# lab5.net
KiCad netlist of a schematic drawn in EAGLE
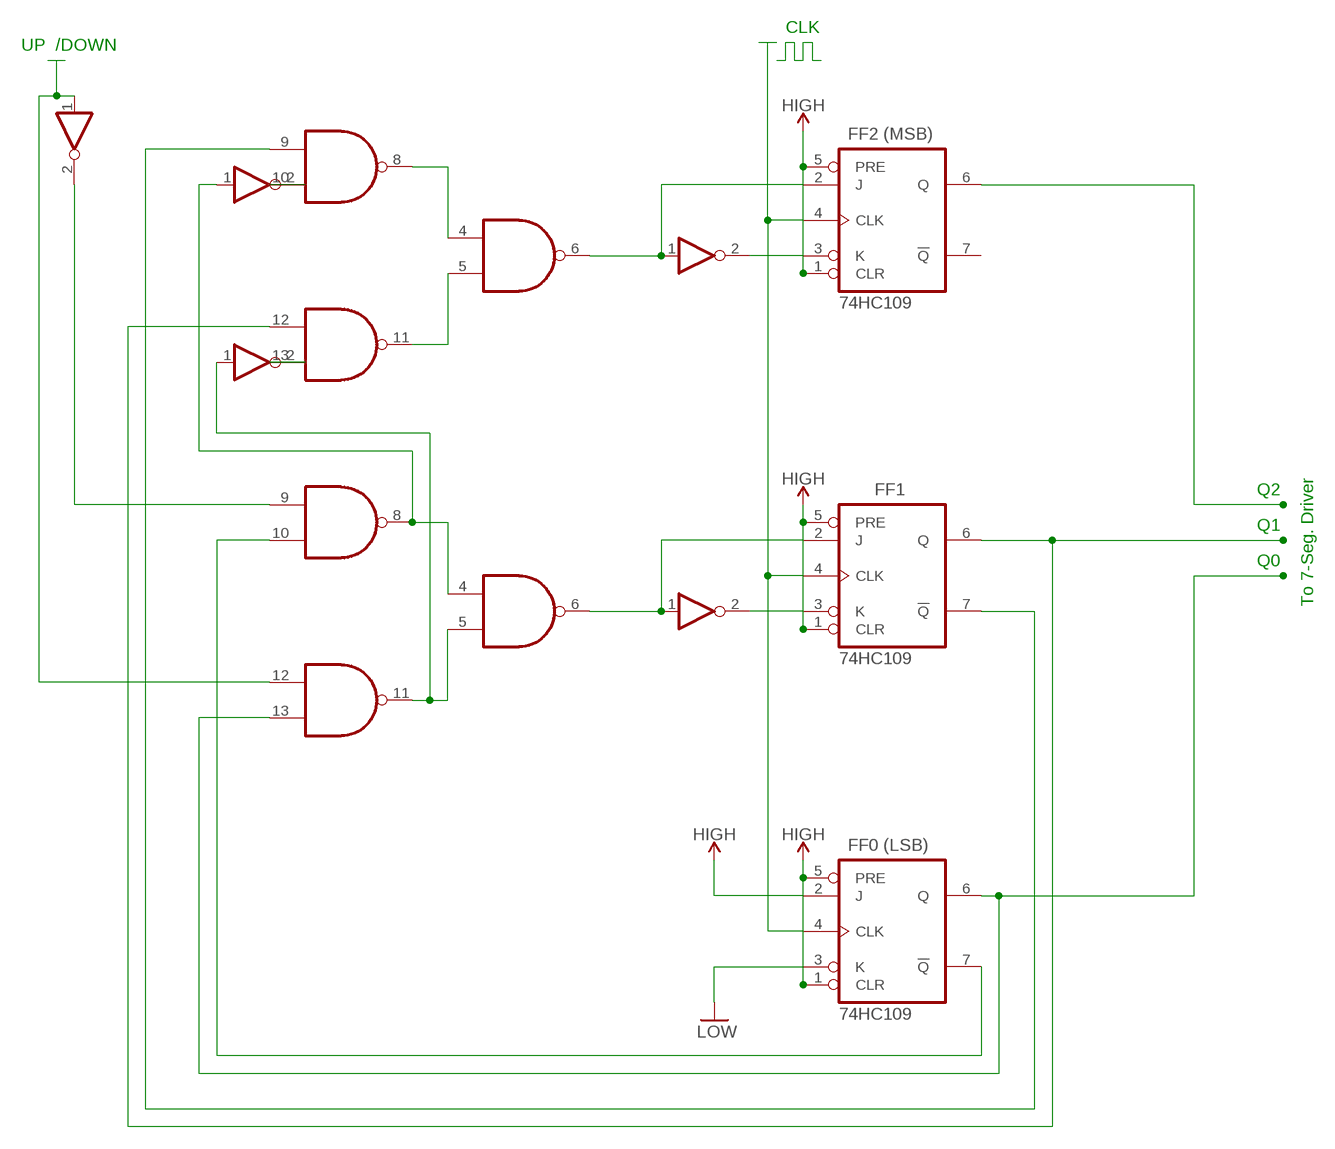
[diagram p0: schematic, sheet 1, part 1 of 2]
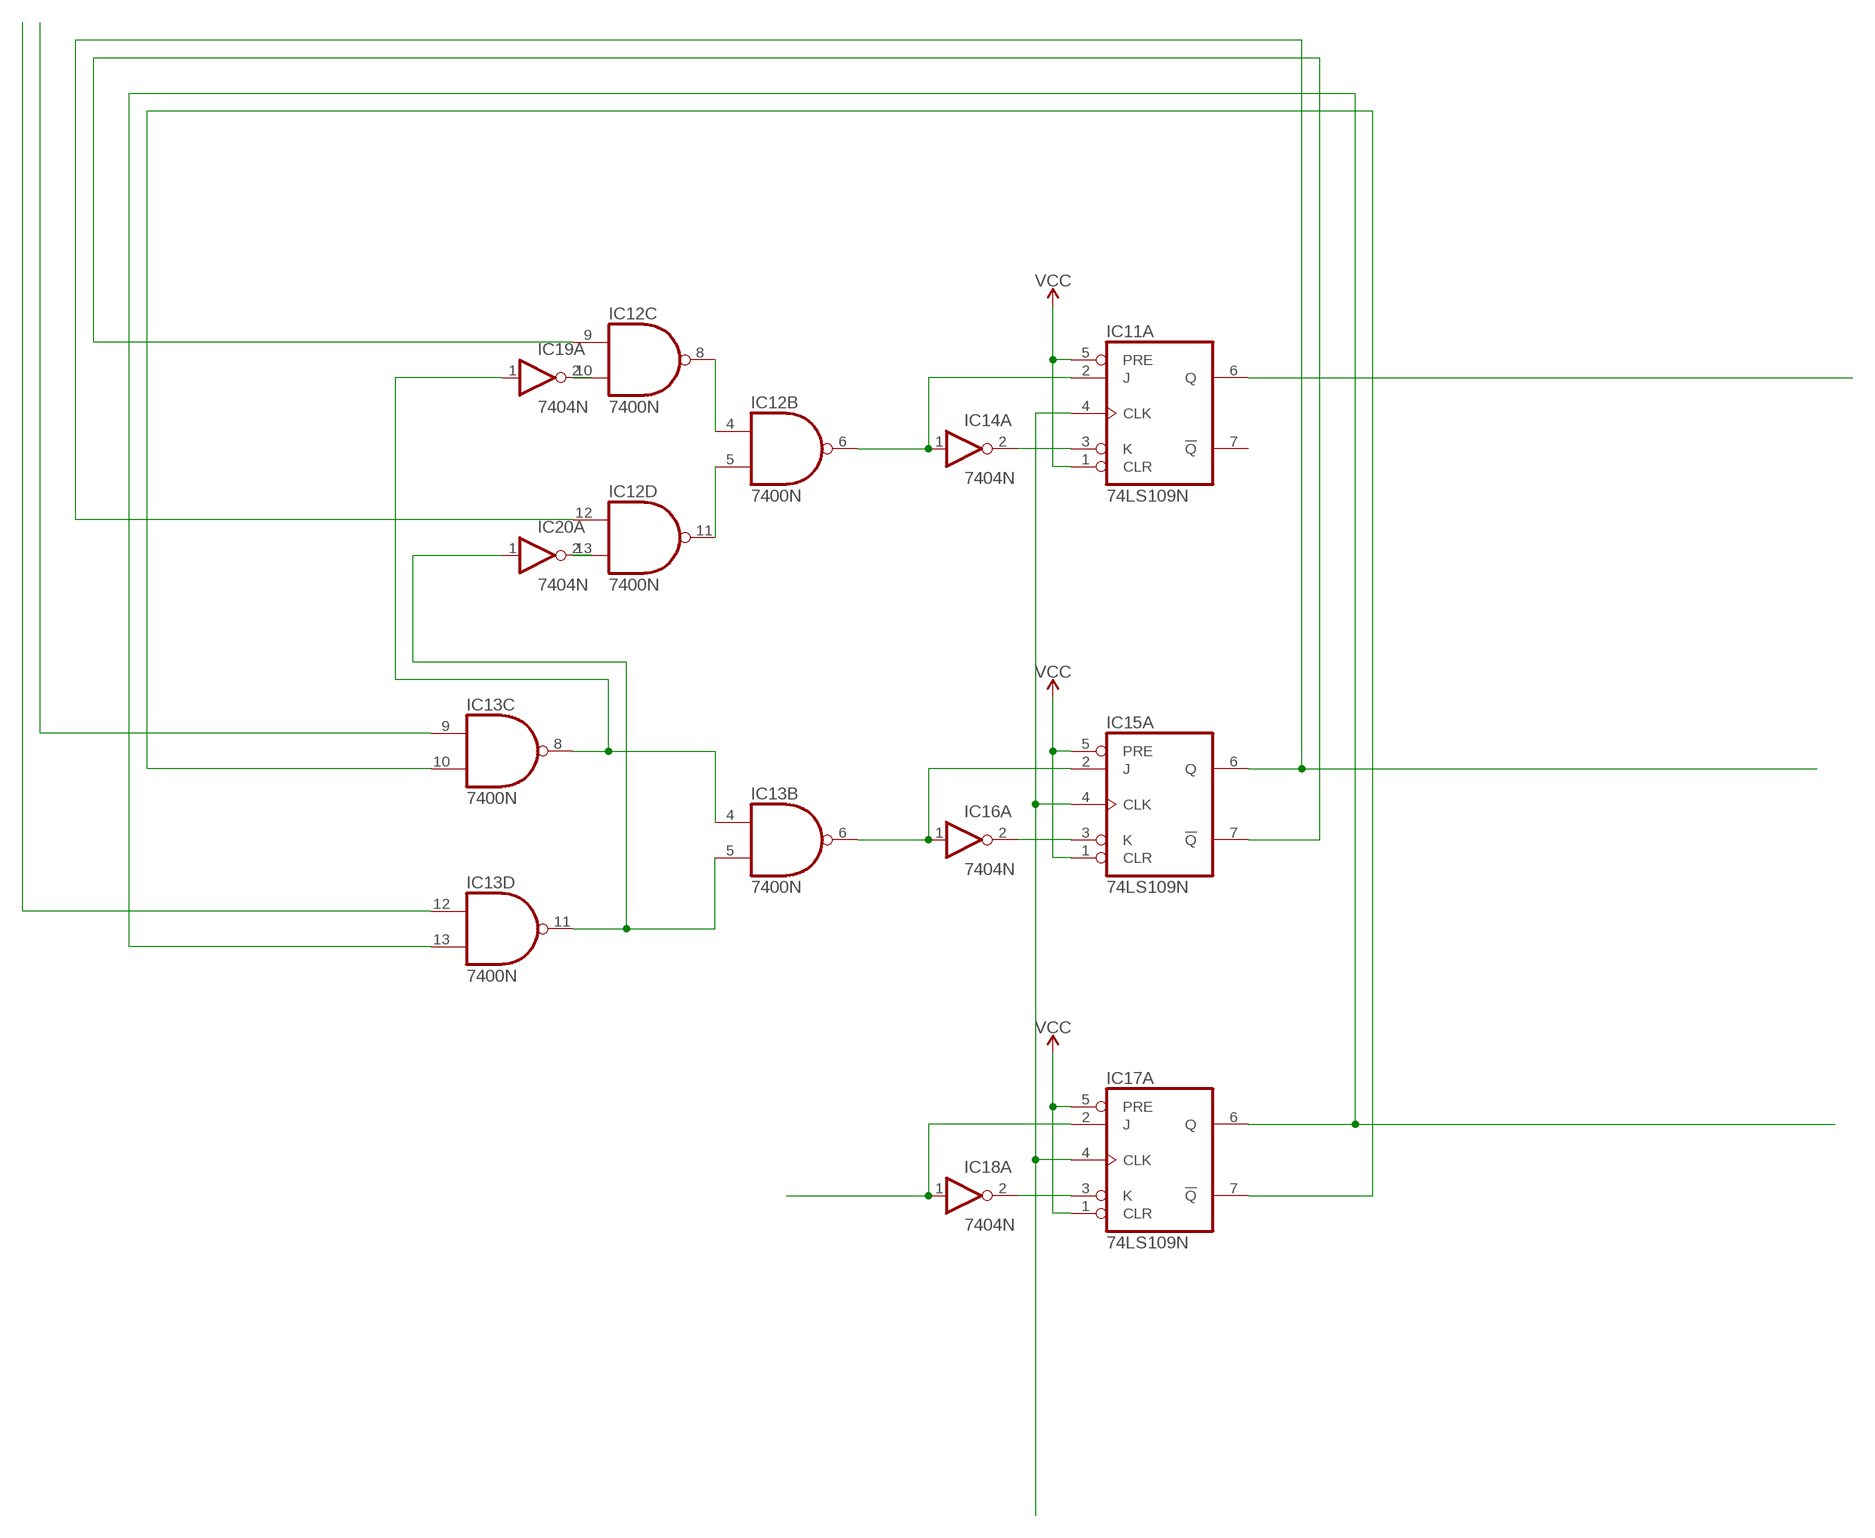
[diagram p1: schematic, sheet 1, part 2 of 2]

(export (version "E")
  (design (tool "Eeschema 10.0.6"))
  (components
    (comp (ref "FF0(LSB)")
      (value "74HC109")
      (footprint "eagle-import:DIL16")
      (libsource (lib "eagle-import") (part "74109NLS"))
    )
    (comp (ref "FF1")
      (value "74HC109")
      (footprint "eagle-import:DIL16")
      (libsource (lib "eagle-import") (part "74109NLS"))
    )
    (comp (ref "FF2(MSB)")
      (value "74HC109")
      (footprint "eagle-import:DIL16")
      (libsource (lib "eagle-import") (part "74109NLS"))
    )
    (comp (ref "IC2")
      (value "7400N")
      (footprint "eagle-import:DIL14")
      (libsource (lib "eagle-import") (part "7400N"))
    )
    (comp (ref "IC4")
      (value "7404N")
      (footprint "eagle-import:DIL14")
      (libsource (lib "eagle-import") (part "7404N"))
    )
    (comp (ref "IC7")
      (value "7400N")
      (footprint "eagle-import:DIL14")
      (libsource (lib "eagle-import") (part "7400N"))
    )
    (comp (ref "IC8")
      (value "7404N")
      (footprint "eagle-import:DIL14")
      (libsource (lib "eagle-import") (part "7404N"))
    )
    (comp (ref "IC9")
      (value "7404N")
      (footprint "eagle-import:DIL14")
      (libsource (lib "eagle-import") (part "7404N"))
    )
    (comp (ref "IC10")
      (value "7404N")
      (footprint "eagle-import:DIL14")
      (libsource (lib "eagle-import") (part "7404N"))
    )
    (comp (ref "IC11")
      (value "74LS109N")
      (footprint "eagle-import:DIL16")
      (libsource (lib "eagle-import") (part "74109NLS"))
    )
    (comp (ref "IC12")
      (value "7400N")
      (footprint "eagle-import:DIL14")
      (libsource (lib "eagle-import") (part "7400N"))
    )
    (comp (ref "IC13")
      (value "7400N")
      (footprint "eagle-import:DIL14")
      (libsource (lib "eagle-import") (part "7400N"))
    )
    (comp (ref "IC14")
      (value "7404N")
      (footprint "eagle-import:DIL14")
      (libsource (lib "eagle-import") (part "7404N"))
    )
    (comp (ref "IC15")
      (value "74LS109N")
      (footprint "eagle-import:DIL16")
      (libsource (lib "eagle-import") (part "74109NLS"))
    )
    (comp (ref "IC16")
      (value "7404N")
      (footprint "eagle-import:DIL14")
      (libsource (lib "eagle-import") (part "7404N"))
    )
    (comp (ref "IC17")
      (value "74LS109N")
      (footprint "eagle-import:DIL16")
      (libsource (lib "eagle-import") (part "74109NLS"))
    )
    (comp (ref "IC18")
      (value "7404N")
      (footprint "eagle-import:DIL14")
      (libsource (lib "eagle-import") (part "7404N"))
    )
    (comp (ref "IC19")
      (value "7404N")
      (footprint "eagle-import:DIL14")
      (libsource (lib "eagle-import") (part "7404N"))
    )
    (comp (ref "IC20")
      (value "7404N")
      (footprint "eagle-import:DIL14")
      (libsource (lib "eagle-import") (part "7404N"))
    )
    (comp (ref "IC21")
      (value "7404N")
      (footprint "eagle-import:DIL14")
      (libsource (lib "eagle-import") (part "7404N"))
    )
  )
  (nets
    (net (code "1") (name "HIGH") (class "Default")
      (node (ref "FF0(LSB)") (pin "1") (pinfunction "CLR_1") (pintype "input"))
      (node (ref "FF0(LSB)") (pin "2") (pinfunction "J_2") (pintype "input"))
      (node (ref "FF0(LSB)") (pin "5") (pinfunction "PRE_5") (pintype "input"))
      (node (ref "FF1") (pin "1") (pinfunction "CLR_1") (pintype "input"))
      (node (ref "FF1") (pin "5") (pinfunction "PRE_5") (pintype "input"))
      (node (ref "FF2(MSB)") (pin "1") (pinfunction "CLR_1") (pintype "input"))
      (node (ref "FF2(MSB)") (pin "5") (pinfunction "PRE_5") (pintype "input"))
      (node (ref "IC11") (pin "1") (pinfunction "CLR_1") (pintype "input"))
      (node (ref "IC11") (pin "5") (pinfunction "PRE_5") (pintype "input"))
      (node (ref "IC15") (pin "1") (pinfunction "CLR_1") (pintype "input"))
      (node (ref "IC15") (pin "5") (pinfunction "PRE_5") (pintype "input"))
      (node (ref "IC17") (pin "1") (pinfunction "CLR_1") (pintype "input"))
      (node (ref "IC17") (pin "5") (pinfunction "PRE_5") (pintype "input"))
    )
    (net (code "2") (name "LOW") (class "Default")
      (node (ref "FF0(LSB)") (pin "3") (pinfunction "K_3") (pintype "input"))
    )
    (net (code "3") (name "Net-(FF0(LSB)A-CLK)") (class "Default")
      (node (ref "FF0(LSB)") (pin "4") (pinfunction "CLK_4") (pintype "input"))
      (node (ref "FF1") (pin "4") (pinfunction "CLK_4") (pintype "input"))
      (node (ref "FF2(MSB)") (pin "4") (pinfunction "CLK_4") (pintype "input"))
    )
    (net (code "4") (name "Net-(FF0(LSB)A-Q)") (class "Default")
      (node (ref "FF0(LSB)") (pin "6") (pinfunction "Q_6") (pintype "output"))
      (node (ref "IC7") (pin "13") (pinfunction "I1_13") (pintype "input"))
    )
    (net (code "5") (name "Net-(FF0(LSB)A-~{Q})") (class "Default")
      (node (ref "FF0(LSB)") (pin "7") (pinfunction "~{Q}_7") (pintype "output"))
      (node (ref "IC7") (pin "10") (pinfunction "I1_10") (pintype "input"))
    )
    (net (code "6") (name "Net-(FF1A-J)") (class "Default")
      (node (ref "FF1") (pin "2") (pinfunction "J_2") (pintype "input"))
      (node (ref "IC7") (pin "6") (pinfunction "O_6") (pintype "output"))
      (node (ref "IC9") (pin "1") (pinfunction "I_1") (pintype "input"))
    )
    (net (code "7") (name "Net-(FF1A-K)") (class "Default")
      (node (ref "FF1") (pin "3") (pinfunction "K_3") (pintype "input"))
      (node (ref "IC9") (pin "2") (pinfunction "O_2") (pintype "output"))
    )
    (net (code "8") (name "Net-(FF1A-Q)") (class "Default")
      (node (ref "FF1") (pin "6") (pinfunction "Q_6") (pintype "output"))
      (node (ref "IC2") (pin "12") (pinfunction "I0_12") (pintype "input"))
    )
    (net (code "9") (name "Net-(FF1A-~{Q})") (class "Default")
      (node (ref "FF1") (pin "7") (pinfunction "~{Q}_7") (pintype "output"))
      (node (ref "IC2") (pin "9") (pinfunction "I0_9") (pintype "input"))
    )
    (net (code "10") (name "Net-(FF2(MSB)A-J)") (class "Default")
      (node (ref "FF2(MSB)") (pin "2") (pinfunction "J_2") (pintype "input"))
      (node (ref "IC2") (pin "6") (pinfunction "O_6") (pintype "output"))
      (node (ref "IC8") (pin "1") (pinfunction "I_1") (pintype "input"))
    )
    (net (code "11") (name "Net-(FF2(MSB)A-K)") (class "Default")
      (node (ref "FF2(MSB)") (pin "3") (pinfunction "K_3") (pintype "input"))
      (node (ref "IC8") (pin "2") (pinfunction "O_2") (pintype "output"))
    )
    (net (code "12") (name "Net-(IC2B-I0)") (class "Default")
      (node (ref "IC2") (pin "4") (pinfunction "I0_4") (pintype "input"))
      (node (ref "IC2") (pin "8") (pinfunction "O_8") (pintype "output"))
    )
    (net (code "13") (name "Net-(IC2B-I1)") (class "Default")
      (node (ref "IC2") (pin "11") (pinfunction "O_11") (pintype "output"))
      (node (ref "IC2") (pin "5") (pinfunction "I1_5") (pintype "input"))
    )
    (net (code "14") (name "Net-(IC2C-I1)") (class "Default")
      (node (ref "IC2") (pin "10") (pinfunction "I1_10") (pintype "input"))
      (node (ref "IC4") (pin "2") (pinfunction "O_2") (pintype "output"))
    )
    (net (code "15") (name "Net-(IC4A-I)") (class "Default")
      (node (ref "IC4") (pin "1") (pinfunction "I_1") (pintype "input"))
      (node (ref "IC7") (pin "4") (pinfunction "I0_4") (pintype "input"))
      (node (ref "IC7") (pin "8") (pinfunction "O_8") (pintype "output"))
    )
    (net (code "16") (name "Net-(IC10A-I)") (class "Default")
      (node (ref "IC10") (pin "1") (pinfunction "I_1") (pintype "input"))
      (node (ref "IC7") (pin "11") (pinfunction "O_11") (pintype "output"))
      (node (ref "IC7") (pin "5") (pinfunction "I1_5") (pintype "input"))
    )
    (net (code "17") (name "Net-(IC10A-O)") (class "Default")
      (node (ref "IC10") (pin "2") (pinfunction "O_2") (pintype "output"))
      (node (ref "IC2") (pin "13") (pinfunction "I1_13") (pintype "input"))
    )
    (net (code "18") (name "Net-(IC11A-CLK)") (class "Default")
      (node (ref "IC11") (pin "4") (pinfunction "CLK_4") (pintype "input"))
      (node (ref "IC15") (pin "4") (pinfunction "CLK_4") (pintype "input"))
      (node (ref "IC17") (pin "4") (pinfunction "CLK_4") (pintype "input"))
    )
    (net (code "19") (name "Net-(IC11A-J)") (class "Default")
      (node (ref "IC11") (pin "2") (pinfunction "J_2") (pintype "input"))
      (node (ref "IC12") (pin "6") (pinfunction "O_6") (pintype "output"))
      (node (ref "IC14") (pin "1") (pinfunction "I_1") (pintype "input"))
    )
    (net (code "20") (name "Net-(IC11A-K)") (class "Default")
      (node (ref "IC11") (pin "3") (pinfunction "K_3") (pintype "input"))
      (node (ref "IC14") (pin "2") (pinfunction "O_2") (pintype "output"))
    )
    (net (code "21") (name "Net-(IC12B-I0)") (class "Default")
      (node (ref "IC12") (pin "4") (pinfunction "I0_4") (pintype "input"))
      (node (ref "IC12") (pin "8") (pinfunction "O_8") (pintype "output"))
    )
    (net (code "22") (name "Net-(IC12B-I1)") (class "Default")
      (node (ref "IC12") (pin "11") (pinfunction "O_11") (pintype "output"))
      (node (ref "IC12") (pin "5") (pinfunction "I1_5") (pintype "input"))
    )
    (net (code "23") (name "Net-(IC12C-I0)") (class "Default")
      (node (ref "IC12") (pin "9") (pinfunction "I0_9") (pintype "input"))
      (node (ref "IC15") (pin "7") (pinfunction "~{Q}_7") (pintype "output"))
    )
    (net (code "24") (name "Net-(IC12C-I1)") (class "Default")
      (node (ref "IC12") (pin "10") (pinfunction "I1_10") (pintype "input"))
      (node (ref "IC19") (pin "2") (pinfunction "O_2") (pintype "output"))
    )
    (net (code "25") (name "Net-(IC12D-I0)") (class "Default")
      (node (ref "IC12") (pin "12") (pinfunction "I0_12") (pintype "input"))
      (node (ref "IC15") (pin "6") (pinfunction "Q_6") (pintype "output"))
    )
    (net (code "26") (name "Net-(IC12D-I1)") (class "Default")
      (node (ref "IC12") (pin "13") (pinfunction "I1_13") (pintype "input"))
      (node (ref "IC20") (pin "2") (pinfunction "O_2") (pintype "output"))
    )
    (net (code "27") (name "Net-(IC13B-I0)") (class "Default")
      (node (ref "IC13") (pin "4") (pinfunction "I0_4") (pintype "input"))
      (node (ref "IC13") (pin "8") (pinfunction "O_8") (pintype "output"))
      (node (ref "IC19") (pin "1") (pinfunction "I_1") (pintype "input"))
    )
    (net (code "28") (name "Net-(IC13B-I1)") (class "Default")
      (node (ref "IC13") (pin "11") (pinfunction "O_11") (pintype "output"))
      (node (ref "IC13") (pin "5") (pinfunction "I1_5") (pintype "input"))
      (node (ref "IC20") (pin "1") (pinfunction "I_1") (pintype "input"))
    )
    (net (code "29") (name "Net-(IC13B-O)") (class "Default")
      (node (ref "IC13") (pin "6") (pinfunction "O_6") (pintype "output"))
      (node (ref "IC15") (pin "2") (pinfunction "J_2") (pintype "input"))
      (node (ref "IC16") (pin "1") (pinfunction "I_1") (pintype "input"))
    )
    (net (code "30") (name "Net-(IC13C-I1)") (class "Default")
      (node (ref "IC13") (pin "10") (pinfunction "I1_10") (pintype "input"))
      (node (ref "IC17") (pin "7") (pinfunction "~{Q}_7") (pintype "output"))
    )
    (net (code "31") (name "Net-(IC13D-I1)") (class "Default")
      (node (ref "IC13") (pin "13") (pinfunction "I1_13") (pintype "input"))
      (node (ref "IC17") (pin "6") (pinfunction "Q_6") (pintype "output"))
    )
    (net (code "32") (name "Net-(IC15A-K)") (class "Default")
      (node (ref "IC15") (pin "3") (pinfunction "K_3") (pintype "input"))
      (node (ref "IC16") (pin "2") (pinfunction "O_2") (pintype "output"))
    )
    (net (code "33") (name "Net-(IC17A-J)") (class "Default")
      (node (ref "IC17") (pin "2") (pinfunction "J_2") (pintype "input"))
      (node (ref "IC18") (pin "1") (pinfunction "I_1") (pintype "input"))
    )
    (net (code "34") (name "Net-(IC17A-K)") (class "Default")
      (node (ref "IC17") (pin "3") (pinfunction "K_3") (pintype "input"))
      (node (ref "IC18") (pin "2") (pinfunction "O_2") (pintype "output"))
    )
    (net (code "35") (name "Net-(IC21A-I)") (class "Default")
      (node (ref "IC21") (pin "1") (pinfunction "I_1") (pintype "input"))
      (node (ref "IC7") (pin "12") (pinfunction "I0_12") (pintype "input"))
    )
    (net (code "36") (name "Net-(IC21A-O)") (class "Default")
      (node (ref "IC21") (pin "2") (pinfunction "O_2") (pintype "output"))
      (node (ref "IC7") (pin "9") (pinfunction "I0_9") (pintype "input"))
    )
    (net (code "37") (name "unconnected-(FF2(MSB)A-Q-Pad6)") (class "Default")
      (node (ref "FF2(MSB)") (pin "6") (pinfunction "Q_6") (pintype "output"))
    )
    (net (code "38") (name "unconnected-(FF2(MSB)A-~{Q}-Pad7)") (class "Default")
      (node (ref "FF2(MSB)") (pin "7") (pinfunction "~{Q}_7") (pintype "output"))
    )
    (net (code "39") (name "unconnected-(IC11A-Q-Pad6)") (class "Default")
      (node (ref "IC11") (pin "6") (pinfunction "Q_6") (pintype "output"))
    )
    (net (code "40") (name "unconnected-(IC11A-~{Q}-Pad7)") (class "Default")
      (node (ref "IC11") (pin "7") (pinfunction "~{Q}_7") (pintype "output"))
    )
    (net (code "41") (name "unconnected-(IC13C-I0-Pad9)") (class "Default")
      (node (ref "IC13") (pin "9") (pinfunction "I0_9") (pintype "input"))
    )
    (net (code "42") (name "unconnected-(IC13D-I0-Pad12)") (class "Default")
      (node (ref "IC13") (pin "12") (pinfunction "I0_12") (pintype "input"))
    )
  )
)
